# OPENMV_MT9V034.net
KiCad netlist of a schematic drawn in Altium Designer
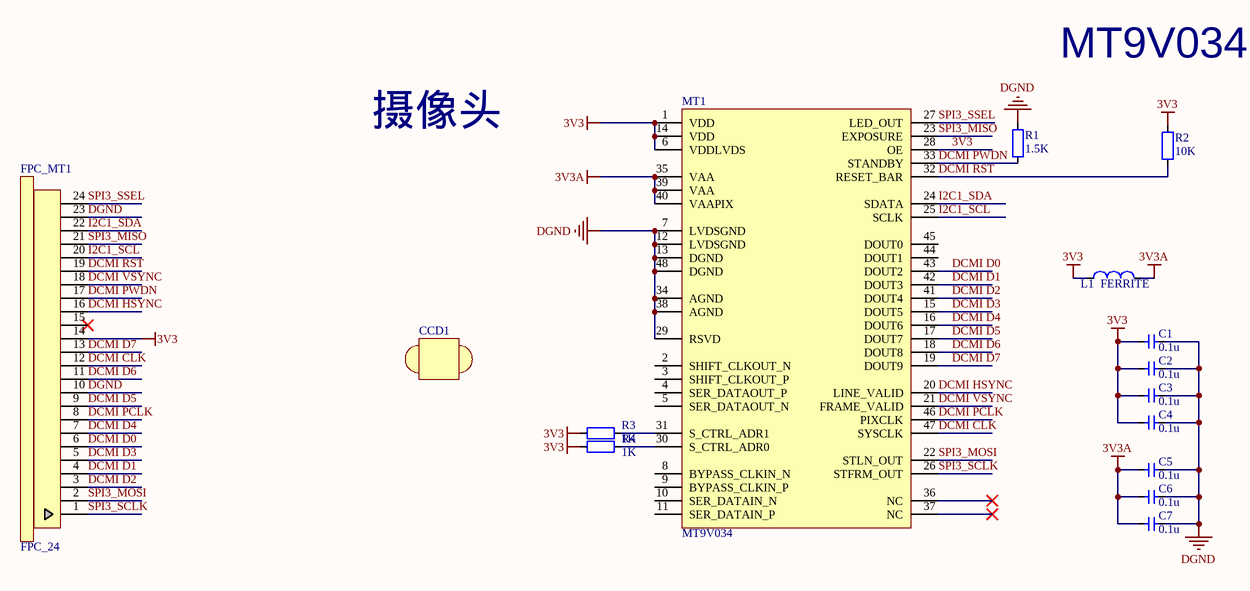
[diagram p0: OPENMV_MT9V034.SchDoc]

(export (version "E")
  (design (tool "Eeschema 10.0.6"))
  (components
    (comp (ref "C1")
      (value "0.1u")
      (footprint "LC-0603_C")
      (description "Capacitor")
      (fields (field (name "Comment") "104"))
      (libsource (lib "SCH_Passive") (part "Cap_0603"))
    )
    (comp (ref "C2")
      (value "0.1u")
      (footprint "LC-0603_C")
      (description "Capacitor")
      (fields (field (name "Comment") "10uF"))
      (libsource (lib "SCH_Passive") (part "Cap_0402"))
    )
    (comp (ref "C3")
      (value "0.1u")
      (footprint "LC-0603_C")
      (description "Capacitor")
      (fields (field (name "Comment") "104"))
      (libsource (lib "SCH_Passive") (part "Cap_0603"))
    )
    (comp (ref "C4")
      (value "0.1u")
      (footprint "LC-0603_C")
      (description "Capacitor")
      (fields (field (name "Comment") "104"))
      (libsource (lib "SCH_Passive") (part "Cap_0603"))
    )
    (comp (ref "C5")
      (value "0.1u")
      (footprint "LC-0603_C")
      (description "Capacitor")
      (fields (field (name "Comment") "104"))
      (libsource (lib "SCH_Passive") (part "Cap_0603"))
    )
    (comp (ref "C6")
      (value "0.1u")
      (footprint "LC-0603_C")
      (description "Capacitor")
      (fields (field (name "Comment") "10uF"))
      (libsource (lib "SCH_Passive") (part "Cap_0603"))
    )
    (comp (ref "C7")
      (value "0.1u")
      (footprint "LC-0603_C")
      (description "Capacitor")
      (fields (field (name "Comment") "104"))
      (libsource (lib "SCH_Passive") (part "Cap_0603"))
    )
    (comp (ref "CCD1")
      (value "CCD")
      (footprint "CCD_LENS_20MM")
      (libsource (lib "SCH_Mechanical") (part "lensCCD_20"))
    )
    (comp (ref "FPC_MT1") (value "FPC_24") (footprint "FPC_24") (libsource (lib "XKZ") (part "FPC_24")))
    (comp (ref "L1")
      (value "FERRITE")
      (footprint "LC-0603_L")
      (description "Inductor")
      (fields (field (name "Comment") "180nH"))
      (libsource (lib "SCH_Passive") (part "Ind_0603"))
    )
    (comp (ref "MT1")
      (value "MT9V034")
      (footprint "CLCC-48")
      (description "CMOS")
      (libsource (lib "SCH_IntegratedCircuit") (part "MT9V034"))
    )
    (comp (ref "R1")
      (value "1.5K")
      (footprint "LC-0603_R")
      (description "Resistor")
      (fields (field (name "Comment") "4.7K"))
      (libsource (lib "") (part "Res_0603_1"))
    )
    (comp (ref "R2")
      (value "10K")
      (footprint "LC-0603_R")
      (description "Resistor")
      (libsource (lib "") (part "Res_0603_1"))
    )
    (comp (ref "R3")
      (value "1K")
      (footprint "LC-0603_R")
      (description "Resistor")
      (libsource (lib "SCH_Passive") (part "Res_0603"))
    )
    (comp (ref "R4")
      (value "1K")
      (footprint "LC-0603_R")
      (description "Resistor")
      (libsource (lib "SCH_Passive") (part "Res_0603"))
    )
  )
  (nets
    (net (code "1") (name "/DCMI CLK") (class "Default")
      (node (ref "FPC_MT1") (pin "12") (pinfunction "12_12") (pintype "passive"))
      (node (ref "MT1") (pin "47") (pinfunction "SYSCLK_47") (pintype "passive"))
    )
    (net (code "2") (name "/DCMI D0") (class "Default")
      (node (ref "FPC_MT1") (pin "6") (pinfunction "6_6") (pintype "passive"))
      (node (ref "MT1") (pin "43") (pinfunction "DOUT2_43") (pintype "passive"))
    )
    (net (code "3") (name "/DCMI D1") (class "Default")
      (node (ref "FPC_MT1") (pin "4") (pinfunction "4_4") (pintype "passive"))
      (node (ref "MT1") (pin "42") (pinfunction "DOUT3_42") (pintype "passive"))
    )
    (net (code "4") (name "/DCMI D2") (class "Default")
      (node (ref "FPC_MT1") (pin "3") (pinfunction "3_3") (pintype "passive"))
      (node (ref "MT1") (pin "41") (pinfunction "DOUT4_41") (pintype "passive"))
    )
    (net (code "5") (name "/DCMI D3") (class "Default")
      (node (ref "FPC_MT1") (pin "5") (pinfunction "5_5") (pintype "passive"))
      (node (ref "MT1") (pin "15") (pinfunction "DOUT5_15") (pintype "passive"))
    )
    (net (code "6") (name "/DCMI D4") (class "Default")
      (node (ref "FPC_MT1") (pin "7") (pinfunction "7_7") (pintype "passive"))
      (node (ref "MT1") (pin "16") (pinfunction "DOUT6_16") (pintype "passive"))
    )
    (net (code "7") (name "/DCMI D5") (class "Default")
      (node (ref "FPC_MT1") (pin "9") (pinfunction "9_9") (pintype "passive"))
      (node (ref "MT1") (pin "17") (pinfunction "DOUT7_17") (pintype "passive"))
    )
    (net (code "8") (name "/DCMI D6") (class "Default")
      (node (ref "FPC_MT1") (pin "11") (pinfunction "11_11") (pintype "passive"))
      (node (ref "MT1") (pin "18") (pinfunction "DOUT8_18") (pintype "passive"))
    )
    (net (code "9") (name "/DCMI D7") (class "Default")
      (node (ref "FPC_MT1") (pin "13") (pinfunction "13_13") (pintype "passive"))
      (node (ref "MT1") (pin "19") (pinfunction "DOUT9_19") (pintype "passive"))
    )
    (net (code "10") (name "/DCMI HSYNC") (class "Default")
      (node (ref "FPC_MT1") (pin "16") (pinfunction "16_16") (pintype "passive"))
      (node (ref "MT1") (pin "20") (pinfunction "LINE_VALID_20") (pintype "passive"))
    )
    (net (code "11") (name "/DCMI PCLK") (class "Default")
      (node (ref "FPC_MT1") (pin "8") (pinfunction "8_8") (pintype "passive"))
      (node (ref "MT1") (pin "46") (pinfunction "PIXCLK_46") (pintype "passive"))
    )
    (net (code "12") (name "/DCMI PWDN") (class "Default")
      (node (ref "FPC_MT1") (pin "17") (pinfunction "17_17") (pintype "passive"))
      (node (ref "MT1") (pin "33") (pinfunction "STANDBY_33") (pintype "passive"))
      (node (ref "R1") (pin "1") (pinfunction "1_1") (pintype "passive"))
    )
    (net (code "13") (name "/DCMI RST") (class "Default")
      (node (ref "FPC_MT1") (pin "19") (pinfunction "19_19") (pintype "passive"))
      (node (ref "MT1") (pin "32") (pinfunction "RESET_BAR_32") (pintype "passive"))
      (node (ref "R2") (pin "1") (pinfunction "1_1") (pintype "passive"))
    )
    (net (code "14") (name "/DCMI VSYNC") (class "Default")
      (node (ref "FPC_MT1") (pin "18") (pinfunction "18_18") (pintype "passive"))
      (node (ref "MT1") (pin "21") (pinfunction "FRAME_VALID_21") (pintype "passive"))
    )
    (net (code "15") (name "/I2C1_SCL") (class "Default")
      (node (ref "FPC_MT1") (pin "20") (pinfunction "20_20") (pintype "passive"))
      (node (ref "MT1") (pin "25") (pinfunction "SCLK_25") (pintype "passive"))
    )
    (net (code "16") (name "/I2C1_SDA") (class "Default")
      (node (ref "FPC_MT1") (pin "22") (pinfunction "22_22") (pintype "passive"))
      (node (ref "MT1") (pin "24") (pinfunction "SDATA_24") (pintype "passive"))
    )
    (net (code "17") (name "/SPI3_MISO") (class "Default")
      (node (ref "FPC_MT1") (pin "21") (pinfunction "21_21") (pintype "passive"))
      (node (ref "MT1") (pin "23") (pinfunction "EXPOSURE_23") (pintype "passive"))
    )
    (net (code "18") (name "/SPI3_MOSI") (class "Default")
      (node (ref "FPC_MT1") (pin "2") (pinfunction "2_2") (pintype "passive"))
      (node (ref "MT1") (pin "22") (pinfunction "STLN_OUT_22") (pintype "passive"))
    )
    (net (code "19") (name "/SPI3_SCLK") (class "Default")
      (node (ref "FPC_MT1") (pin "1") (pinfunction "1_1") (pintype "passive"))
      (node (ref "MT1") (pin "26") (pinfunction "STFRM_OUT_26") (pintype "passive"))
    )
    (net (code "20") (name "/SPI3_SSEL") (class "Default")
      (node (ref "FPC_MT1") (pin "24") (pinfunction "24_24") (pintype "passive"))
      (node (ref "MT1") (pin "27") (pinfunction "LED_OUT_27") (pintype "passive"))
    )
    (net (code "21") (name "3V3") (class "Default")
      (node (ref "C1") (pin "2") (pinfunction "2_2") (pintype "passive"))
      (node (ref "C2") (pin "2") (pinfunction "2_2") (pintype "passive"))
      (node (ref "C3") (pin "2") (pinfunction "2_2") (pintype "passive"))
      (node (ref "C4") (pin "2") (pinfunction "2_2") (pintype "passive"))
      (node (ref "FPC_MT1") (pin "14") (pinfunction "14_14") (pintype "passive"))
      (node (ref "L1") (pin "1") (pinfunction "1_1") (pintype "passive"))
      (node (ref "MT1") (pin "1") (pinfunction "VDD_1") (pintype "passive"))
      (node (ref "MT1") (pin "14") (pinfunction "VDD_14") (pintype "passive"))
      (node (ref "MT1") (pin "28") (pinfunction "OE_28") (pintype "passive"))
      (node (ref "MT1") (pin "6") (pinfunction "VDDLVDS_6") (pintype "passive"))
      (node (ref "R2") (pin "2") (pinfunction "2_2") (pintype "passive"))
      (node (ref "R3") (pin "2") (pinfunction "2_2") (pintype "passive"))
      (node (ref "R4") (pin "2") (pinfunction "2_2") (pintype "passive"))
    )
    (net (code "22") (name "3V3A") (class "Default")
      (node (ref "C5") (pin "2") (pinfunction "2_2") (pintype "passive"))
      (node (ref "C6") (pin "2") (pinfunction "2_2") (pintype "passive"))
      (node (ref "C7") (pin "2") (pinfunction "2_2") (pintype "passive"))
      (node (ref "L1") (pin "2") (pinfunction "2_2") (pintype "passive"))
      (node (ref "MT1") (pin "35") (pinfunction "VAA_35") (pintype "passive"))
      (node (ref "MT1") (pin "39") (pinfunction "VAA_39") (pintype "passive"))
      (node (ref "MT1") (pin "40") (pinfunction "VAAPIX_40") (pintype "passive"))
    )
    (net (code "23") (name "DGND") (class "Default")
      (node (ref "C1") (pin "1") (pinfunction "1_1") (pintype "passive"))
      (node (ref "C2") (pin "1") (pinfunction "1_1") (pintype "passive"))
      (node (ref "C3") (pin "1") (pinfunction "1_1") (pintype "passive"))
      (node (ref "C4") (pin "1") (pinfunction "1_1") (pintype "passive"))
      (node (ref "C5") (pin "1") (pinfunction "1_1") (pintype "passive"))
      (node (ref "C6") (pin "1") (pinfunction "1_1") (pintype "passive"))
      (node (ref "C7") (pin "1") (pinfunction "1_1") (pintype "passive"))
      (node (ref "FPC_MT1") (pin "10") (pinfunction "10_10") (pintype "passive"))
      (node (ref "FPC_MT1") (pin "23") (pinfunction "23_23") (pintype "passive"))
      (node (ref "MT1") (pin "12") (pinfunction "LVDSGND_12") (pintype "passive"))
      (node (ref "MT1") (pin "13") (pinfunction "DGND_13") (pintype "passive"))
      (node (ref "MT1") (pin "29") (pinfunction "RSVD_29") (pintype "passive"))
      (node (ref "MT1") (pin "34") (pinfunction "AGND_34") (pintype "passive"))
      (node (ref "MT1") (pin "38") (pinfunction "AGND_38") (pintype "passive"))
      (node (ref "MT1") (pin "48") (pinfunction "DGND_48") (pintype "passive"))
      (node (ref "MT1") (pin "7") (pinfunction "LVDSGND_7") (pintype "passive"))
      (node (ref "R1") (pin "2") (pinfunction "2_2") (pintype "passive"))
    )
    (net (code "24") (name "Net-(MT1-S_CTRL_ADR0)") (class "Default")
      (node (ref "MT1") (pin "30") (pinfunction "S_CTRL_ADR0_30") (pintype "passive"))
      (node (ref "R4") (pin "1") (pinfunction "1_1") (pintype "passive"))
    )
    (net (code "25") (name "Net-(MT1-S_CTRL_ADR1)") (class "Default")
      (node (ref "MT1") (pin "31") (pinfunction "S_CTRL_ADR1_31") (pintype "passive"))
      (node (ref "R3") (pin "1") (pinfunction "1_1") (pintype "passive"))
    )
    (net (code "26") (name "unconnected-(FPC_MT1-Pad15)") (class "Default")
      (node (ref "FPC_MT1") (pin "15") (pinfunction "15_15") (pintype "passive+no_connect"))
    )
    (net (code "27") (name "unconnected-(MT1-BYPASS_CLKIN_N-Pad8)") (class "Default")
      (node (ref "MT1") (pin "8") (pinfunction "BYPASS_CLKIN_N_8") (pintype "passive"))
    )
    (net (code "28") (name "unconnected-(MT1-BYPASS_CLKIN_P-Pad9)") (class "Default")
      (node (ref "MT1") (pin "9") (pinfunction "BYPASS_CLKIN_P_9") (pintype "passive"))
    )
    (net (code "29") (name "unconnected-(MT1-DOUT0-Pad45)") (class "Default")
      (node (ref "MT1") (pin "45") (pinfunction "DOUT0_45") (pintype "passive"))
    )
    (net (code "30") (name "unconnected-(MT1-DOUT1-Pad44)") (class "Default")
      (node (ref "MT1") (pin "44") (pinfunction "DOUT1_44") (pintype "passive"))
    )
    (net (code "31") (name "unconnected-(MT1-NC-Pad36)") (class "Default")
      (node (ref "MT1") (pin "36") (pinfunction "NC_36") (pintype "passive+no_connect"))
    )
    (net (code "32") (name "unconnected-(MT1-NC-Pad37)") (class "Default")
      (node (ref "MT1") (pin "37") (pinfunction "NC_37") (pintype "passive+no_connect"))
    )
    (net (code "33") (name "unconnected-(MT1-SER_DATAIN_N-Pad10)") (class "Default")
      (node (ref "MT1") (pin "10") (pinfunction "SER_DATAIN_N_10") (pintype "passive"))
    )
    (net (code "34") (name "unconnected-(MT1-SER_DATAIN_P-Pad11)") (class "Default")
      (node (ref "MT1") (pin "11") (pinfunction "SER_DATAIN_P_11") (pintype "passive"))
    )
    (net (code "35") (name "unconnected-(MT1-SER_DATAOUT_N-Pad5)") (class "Default")
      (node (ref "MT1") (pin "5") (pinfunction "SER_DATAOUT_N_5") (pintype "passive"))
    )
    (net (code "36") (name "unconnected-(MT1-SER_DATAOUT_P-Pad4)") (class "Default")
      (node (ref "MT1") (pin "4") (pinfunction "SER_DATAOUT_P_4") (pintype "passive"))
    )
    (net (code "37") (name "unconnected-(MT1-SHIFT_CLKOUT_N-Pad2)") (class "Default")
      (node (ref "MT1") (pin "2") (pinfunction "SHIFT_CLKOUT_N_2") (pintype "passive"))
    )
    (net (code "38") (name "unconnected-(MT1-SHIFT_CLKOUT_P-Pad3)") (class "Default")
      (node (ref "MT1") (pin "3") (pinfunction "SHIFT_CLKOUT_P_3") (pintype "passive"))
    )
  )
)
